# EthTransformers.net
KiCad netlist of a schematic drawn in Altium Designer
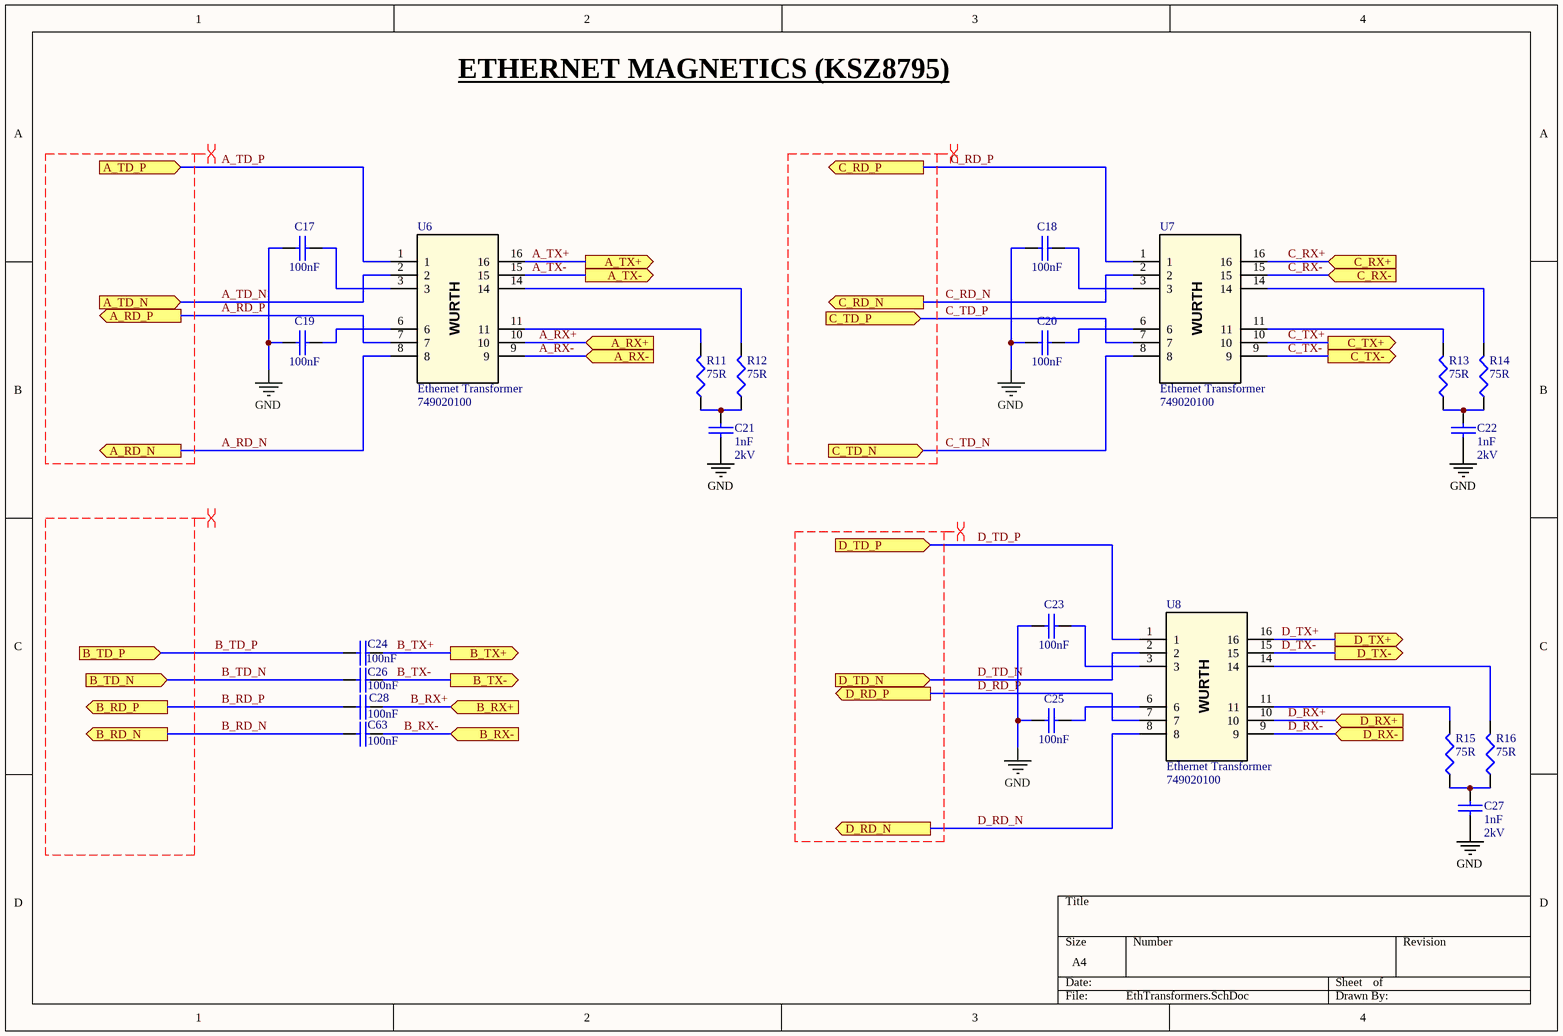
[diagram p0: EthTransformers.SchDoc]

(export (version "E")
  (design (tool "Eeschema 10.0.6"))
  (components
    (comp (ref "C17")
      (value "Capacitor")
      (footprint "CAP0402")
      (fields
        (field (name "MANUFACTURER") "TDK")
        (field (name "MANUFACTURER PART NUMBER") "CGA2B3X7R1H104K050BB")
        (field (name "CAPACITANCE") "100nF")
        (field (name "TOLERANCE") "10%")
      )
      (libsource (lib "BPL-ShematicLibrary") (part "Capacitor"))
    )
    (comp (ref "C18")
      (value "Capacitor")
      (footprint "CAP0402")
      (fields
        (field (name "MANUFACTURER") "TDK")
        (field (name "MANUFACTURER PART NUMBER") "CGA2B3X7R1H104K050BB")
        (field (name "CAPACITANCE") "100nF")
        (field (name "TOLERANCE") "10%")
      )
      (libsource (lib "BPL-ShematicLibrary") (part "Capacitor"))
    )
    (comp (ref "C19")
      (value "Capacitor")
      (footprint "CAP0402")
      (fields
        (field (name "MANUFACTURER") "TDK")
        (field (name "MANUFACTURER PART NUMBER") "CGA2B3X7R1H104K050BB")
        (field (name "CAPACITANCE") "100nF")
        (field (name "TOLERANCE") "10%")
      )
      (libsource (lib "BPL-ShematicLibrary") (part "Capacitor"))
    )
    (comp (ref "C20")
      (value "Capacitor")
      (footprint "CAP0402")
      (fields
        (field (name "MANUFACTURER") "TDK")
        (field (name "MANUFACTURER PART NUMBER") "CGA2B3X7R1H104K050BB")
        (field (name "CAPACITANCE") "100nF")
        (field (name "TOLERANCE") "10%")
      )
      (libsource (lib "BPL-ShematicLibrary") (part "Capacitor"))
    )
    (comp (ref "C21")
      (value "Capacitor")
      (footprint "CAP1206")
      (fields (field (name "CAPACITANCE") "1nF") (field (name "VOLTAGE RATING (DC)") "2kV"))
      (libsource (lib "BPL-ShematicLibrary") (part "Capacitor"))
    )
    (comp (ref "C22")
      (value "Capacitor")
      (footprint "CAP1206")
      (fields (field (name "CAPACITANCE") "1nF") (field (name "VOLTAGE RATING (DC)") "2kV"))
      (libsource (lib "BPL-ShematicLibrary") (part "Capacitor"))
    )
    (comp (ref "C23")
      (value "Capacitor")
      (footprint "CAP0402")
      (fields
        (field (name "MANUFACTURER") "TDK")
        (field (name "MANUFACTURER PART NUMBER") "CGA2B3X7R1H104K050BB")
        (field (name "CAPACITANCE") "100nF")
        (field (name "TOLERANCE") "10%")
      )
      (libsource (lib "BPL-ShematicLibrary") (part "Capacitor"))
    )
    (comp (ref "C24")
      (value "Capacitor")
      (footprint "CAP0402")
      (fields
        (field (name "MANUFACTURER") "TDK")
        (field (name "MANUFACTURER PART NUMBER") "CGA2B3X7R1H104K050BB")
        (field (name "CAPACITANCE") "100nF")
        (field (name "TOLERANCE") "10%")
      )
      (libsource (lib "BPL-ShematicLibrary") (part "Capacitor"))
    )
    (comp (ref "C25")
      (value "Capacitor")
      (footprint "CAP0402")
      (fields
        (field (name "MANUFACTURER") "TDK")
        (field (name "MANUFACTURER PART NUMBER") "CGA2B3X7R1H104K050BB")
        (field (name "CAPACITANCE") "100nF")
        (field (name "TOLERANCE") "10%")
      )
      (libsource (lib "BPL-ShematicLibrary") (part "Capacitor"))
    )
    (comp (ref "C26")
      (value "Capacitor")
      (footprint "CAP0402")
      (fields
        (field (name "MANUFACTURER") "TDK")
        (field (name "MANUFACTURER PART NUMBER") "CGA2B3X7R1H104K050BB")
        (field (name "CAPACITANCE") "100nF")
        (field (name "TOLERANCE") "10%")
      )
      (libsource (lib "BPL-ShematicLibrary") (part "Capacitor"))
    )
    (comp (ref "C27")
      (value "Capacitor")
      (footprint "CAP1206")
      (fields (field (name "CAPACITANCE") "1nF") (field (name "VOLTAGE RATING (DC)") "2kV"))
      (libsource (lib "BPL-ShematicLibrary") (part "Capacitor"))
    )
    (comp (ref "C28")
      (value "Capacitor")
      (footprint "CAP0402")
      (fields
        (field (name "MANUFACTURER") "TDK")
        (field (name "MANUFACTURER PART NUMBER") "CGA2B3X7R1H104K050BB")
        (field (name "CAPACITANCE") "100nF")
        (field (name "TOLERANCE") "10%")
      )
      (libsource (lib "BPL-ShematicLibrary") (part "Capacitor"))
    )
    (comp (ref "C63")
      (value "Capacitor")
      (footprint "CAP0402")
      (fields
        (field (name "MANUFACTURER") "TDK")
        (field (name "MANUFACTURER PART NUMBER") "CGA2B3X7R1H104K050BB")
        (field (name "CAPACITANCE") "100nF")
        (field (name "TOLERANCE") "10%")
      )
      (libsource (lib "BPL-ShematicLibrary") (part "Capacitor"))
    )
    (comp (ref "R11")
      (value "Res")
      (footprint "RES0402")
      (description "Resistor")
      (fields
        (field (name "MANUFACTURER") "Yageo")
        (field (name "MANUFACTURER PART NUMBER") "RC0402FR-0775RL")
        (field (name "RESISTANCE") "75R")
      )
      (libsource (lib "BPL-ShematicLibrary") (part "Resistor"))
    )
    (comp (ref "R12")
      (value "Res")
      (footprint "RES0402")
      (description "Resistor")
      (fields
        (field (name "MANUFACTURER") "Yageo")
        (field (name "MANUFACTURER PART NUMBER") "RC0402FR-0775RL")
        (field (name "RESISTANCE") "75R")
      )
      (libsource (lib "BPL-ShematicLibrary") (part "Resistor"))
    )
    (comp (ref "R13")
      (value "Res")
      (footprint "RES0402")
      (description "Resistor")
      (fields
        (field (name "MANUFACTURER") "Yageo")
        (field (name "MANUFACTURER PART NUMBER") "RC0402FR-0775RL")
        (field (name "RESISTANCE") "75R")
      )
      (libsource (lib "BPL-ShematicLibrary") (part "Resistor"))
    )
    (comp (ref "R14")
      (value "Res")
      (footprint "RES0402")
      (description "Resistor")
      (fields
        (field (name "MANUFACTURER") "Yageo")
        (field (name "MANUFACTURER PART NUMBER") "RC0402FR-0775RL")
        (field (name "RESISTANCE") "75R")
      )
      (libsource (lib "BPL-ShematicLibrary") (part "Resistor"))
    )
    (comp (ref "R15")
      (value "Res")
      (footprint "RES0402")
      (description "Resistor")
      (fields
        (field (name "MANUFACTURER") "Yageo")
        (field (name "MANUFACTURER PART NUMBER") "RC0402FR-0775RL")
        (field (name "RESISTANCE") "75R")
      )
      (libsource (lib "BPL-ShematicLibrary") (part "Resistor"))
    )
    (comp (ref "R16")
      (value "Res")
      (footprint "RES0402")
      (description "Resistor")
      (fields
        (field (name "MANUFACTURER") "Yageo")
        (field (name "MANUFACTURER PART NUMBER") "RC0402FR-0775RL")
        (field (name "RESISTANCE") "75R")
      )
      (libsource (lib "BPL-ShematicLibrary") (part "Resistor"))
    )
    (comp (ref "U6")
      (value "Ethernet Transformer")
      (footprint "749020100")
      (description "350µH LAN 10/100/1000 Base-T Pulse Transformer 1:1 Surface Mount")
      (fields (field (name "MANUFACTURER PART NUMBER 1") "749020100"))
      (libsource (lib "BPL-ShematicLibrary") (part "749020100"))
    )
    (comp (ref "U7")
      (value "Ethernet Transformer")
      (footprint "749020100")
      (description "350µH LAN 10/100/1000 Base-T Pulse Transformer 1:1 Surface Mount")
      (fields (field (name "MANUFACTURER PART NUMBER 1") "749020100"))
      (libsource (lib "BPL-ShematicLibrary") (part "749020100"))
    )
    (comp (ref "U8")
      (value "Ethernet Transformer")
      (footprint "749020100")
      (description "350µH LAN 10/100/1000 Base-T Pulse Transformer 1:1 Surface Mount")
      (fields (field (name "MANUFACTURER PART NUMBER 1") "749020100"))
      (libsource (lib "BPL-ShematicLibrary") (part "749020100"))
    )
  )
  (nets
    (net (code "1") (name "/A_RD_N") (class "Default")
      (node (ref "U6") (pin "8") (pinfunction "8_8") (pintype "passive"))
    )
    (net (code "2") (name "/A_RD_P") (class "Default")
      (node (ref "U6") (pin "7") (pinfunction "7_7") (pintype "passive"))
    )
    (net (code "3") (name "/A_RX+") (class "Default")
      (node (ref "U6") (pin "10") (pinfunction "10_10") (pintype "passive"))
    )
    (net (code "4") (name "/A_RX-") (class "Default")
      (node (ref "U6") (pin "9") (pinfunction "9_9") (pintype "passive"))
    )
    (net (code "5") (name "/A_TD_N") (class "Default")
      (node (ref "U6") (pin "2") (pinfunction "2_2") (pintype "passive"))
    )
    (net (code "6") (name "/A_TD_P") (class "Default")
      (node (ref "U6") (pin "1") (pinfunction "1_1") (pintype "passive"))
    )
    (net (code "7") (name "/A_TX+") (class "Default")
      (node (ref "U6") (pin "16") (pinfunction "16_16") (pintype "passive"))
    )
    (net (code "8") (name "/A_TX-") (class "Default")
      (node (ref "U6") (pin "15") (pinfunction "15_15") (pintype "passive"))
    )
    (net (code "9") (name "/B_RD_N") (class "Default")
      (node (ref "C63") (pin "2") (pinfunction "2_2") (pintype "passive"))
    )
    (net (code "10") (name "/B_RD_P") (class "Default")
      (node (ref "C28") (pin "2") (pinfunction "2_2") (pintype "passive"))
    )
    (net (code "11") (name "/B_RX+") (class "Default")
      (node (ref "C28") (pin "1") (pinfunction "1_1") (pintype "passive"))
    )
    (net (code "12") (name "/B_RX-") (class "Default")
      (node (ref "C63") (pin "1") (pinfunction "1_1") (pintype "passive"))
    )
    (net (code "13") (name "/B_TD_N") (class "Default")
      (node (ref "C26") (pin "2") (pinfunction "2_2") (pintype "passive"))
    )
    (net (code "14") (name "/B_TD_P") (class "Default")
      (node (ref "C24") (pin "2") (pinfunction "2_2") (pintype "passive"))
    )
    (net (code "15") (name "/B_TX+") (class "Default")
      (node (ref "C24") (pin "1") (pinfunction "1_1") (pintype "passive"))
    )
    (net (code "16") (name "/B_TX-") (class "Default")
      (node (ref "C26") (pin "1") (pinfunction "1_1") (pintype "passive"))
    )
    (net (code "17") (name "/C_RD_N") (class "Default")
      (node (ref "U7") (pin "2") (pinfunction "2_2") (pintype "passive"))
    )
    (net (code "18") (name "/C_RD_P") (class "Default")
      (node (ref "U7") (pin "1") (pinfunction "1_1") (pintype "passive"))
    )
    (net (code "19") (name "/C_RX+") (class "Default")
      (node (ref "U7") (pin "16") (pinfunction "16_16") (pintype "passive"))
    )
    (net (code "20") (name "/C_RX-") (class "Default")
      (node (ref "U7") (pin "15") (pinfunction "15_15") (pintype "passive"))
    )
    (net (code "21") (name "/C_TD_N") (class "Default")
      (node (ref "U7") (pin "8") (pinfunction "8_8") (pintype "passive"))
    )
    (net (code "22") (name "/C_TD_P") (class "Default")
      (node (ref "U7") (pin "7") (pinfunction "7_7") (pintype "passive"))
    )
    (net (code "23") (name "/C_TX+") (class "Default")
      (node (ref "U7") (pin "10") (pinfunction "10_10") (pintype "passive"))
    )
    (net (code "24") (name "/C_TX-") (class "Default")
      (node (ref "U7") (pin "9") (pinfunction "9_9") (pintype "passive"))
    )
    (net (code "25") (name "/D_RD_N") (class "Default")
      (node (ref "U8") (pin "8") (pinfunction "8_8") (pintype "passive"))
    )
    (net (code "26") (name "/D_RD_P") (class "Default")
      (node (ref "U8") (pin "7") (pinfunction "7_7") (pintype "passive"))
    )
    (net (code "27") (name "/D_RX+") (class "Default")
      (node (ref "U8") (pin "10") (pinfunction "10_10") (pintype "passive"))
    )
    (net (code "28") (name "/D_RX-") (class "Default")
      (node (ref "U8") (pin "9") (pinfunction "9_9") (pintype "passive"))
    )
    (net (code "29") (name "/D_TD_N") (class "Default")
      (node (ref "U8") (pin "2") (pinfunction "2_2") (pintype "passive"))
    )
    (net (code "30") (name "/D_TD_P") (class "Default")
      (node (ref "U8") (pin "1") (pinfunction "1_1") (pintype "passive"))
    )
    (net (code "31") (name "/D_TX+") (class "Default")
      (node (ref "U8") (pin "16") (pinfunction "16_16") (pintype "passive"))
    )
    (net (code "32") (name "/D_TX-") (class "Default")
      (node (ref "U8") (pin "15") (pinfunction "15_15") (pintype "passive"))
    )
    (net (code "33") (name "GND") (class "Default")
      (node (ref "C17") (pin "2") (pinfunction "2_2") (pintype "passive"))
      (node (ref "C18") (pin "2") (pinfunction "2_2") (pintype "passive"))
      (node (ref "C19") (pin "2") (pinfunction "2_2") (pintype "passive"))
      (node (ref "C20") (pin "2") (pinfunction "2_2") (pintype "passive"))
      (node (ref "C21") (pin "2") (pinfunction "2_2") (pintype "passive"))
      (node (ref "C22") (pin "2") (pinfunction "2_2") (pintype "passive"))
      (node (ref "C23") (pin "2") (pinfunction "2_2") (pintype "passive"))
      (node (ref "C25") (pin "2") (pinfunction "2_2") (pintype "passive"))
      (node (ref "C27") (pin "2") (pinfunction "2_2") (pintype "passive"))
    )
    (net (code "34") (name "Net-(C17-Pad1)") (class "Default")
      (node (ref "C17") (pin "1") (pinfunction "1_1") (pintype "passive"))
      (node (ref "U6") (pin "3") (pinfunction "3_3") (pintype "passive"))
    )
    (net (code "35") (name "Net-(C18-Pad1)") (class "Default")
      (node (ref "C18") (pin "1") (pinfunction "1_1") (pintype "passive"))
      (node (ref "U7") (pin "3") (pinfunction "3_3") (pintype "passive"))
    )
    (net (code "36") (name "Net-(C19-Pad1)") (class "Default")
      (node (ref "C19") (pin "1") (pinfunction "1_1") (pintype "passive"))
      (node (ref "U6") (pin "6") (pinfunction "6_6") (pintype "passive"))
    )
    (net (code "37") (name "Net-(C20-Pad1)") (class "Default")
      (node (ref "C20") (pin "1") (pinfunction "1_1") (pintype "passive"))
      (node (ref "U7") (pin "6") (pinfunction "6_6") (pintype "passive"))
    )
    (net (code "38") (name "Net-(C21-Pad1)") (class "Default")
      (node (ref "C21") (pin "1") (pinfunction "1_1") (pintype "passive"))
      (node (ref "R11") (pin "1") (pinfunction "1_1") (pintype "passive"))
      (node (ref "R12") (pin "1") (pinfunction "1_1") (pintype "passive"))
    )
    (net (code "39") (name "Net-(C22-Pad1)") (class "Default")
      (node (ref "C22") (pin "1") (pinfunction "1_1") (pintype "passive"))
      (node (ref "R13") (pin "1") (pinfunction "1_1") (pintype "passive"))
      (node (ref "R14") (pin "1") (pinfunction "1_1") (pintype "passive"))
    )
    (net (code "40") (name "Net-(C23-Pad1)") (class "Default")
      (node (ref "C23") (pin "1") (pinfunction "1_1") (pintype "passive"))
      (node (ref "U8") (pin "3") (pinfunction "3_3") (pintype "passive"))
    )
    (net (code "41") (name "Net-(C25-Pad1)") (class "Default")
      (node (ref "C25") (pin "1") (pinfunction "1_1") (pintype "passive"))
      (node (ref "U8") (pin "6") (pinfunction "6_6") (pintype "passive"))
    )
    (net (code "42") (name "Net-(C27-Pad1)") (class "Default")
      (node (ref "C27") (pin "1") (pinfunction "1_1") (pintype "passive"))
      (node (ref "R15") (pin "1") (pinfunction "1_1") (pintype "passive"))
      (node (ref "R16") (pin "1") (pinfunction "1_1") (pintype "passive"))
    )
    (net (code "43") (name "Net-(R11-Pad2)") (class "Default")
      (node (ref "R11") (pin "2") (pinfunction "2_2") (pintype "passive"))
      (node (ref "U6") (pin "11") (pinfunction "11_11") (pintype "passive"))
    )
    (net (code "44") (name "Net-(R12-Pad2)") (class "Default")
      (node (ref "R12") (pin "2") (pinfunction "2_2") (pintype "passive"))
      (node (ref "U6") (pin "14") (pinfunction "14_14") (pintype "passive"))
    )
    (net (code "45") (name "Net-(R13-Pad2)") (class "Default")
      (node (ref "R13") (pin "2") (pinfunction "2_2") (pintype "passive"))
      (node (ref "U7") (pin "11") (pinfunction "11_11") (pintype "passive"))
    )
    (net (code "46") (name "Net-(R14-Pad2)") (class "Default")
      (node (ref "R14") (pin "2") (pinfunction "2_2") (pintype "passive"))
      (node (ref "U7") (pin "14") (pinfunction "14_14") (pintype "passive"))
    )
    (net (code "47") (name "Net-(R15-Pad2)") (class "Default")
      (node (ref "R15") (pin "2") (pinfunction "2_2") (pintype "passive"))
      (node (ref "U8") (pin "11") (pinfunction "11_11") (pintype "passive"))
    )
    (net (code "48") (name "Net-(R16-Pad2)") (class "Default")
      (node (ref "R16") (pin "2") (pinfunction "2_2") (pintype "passive"))
      (node (ref "U8") (pin "14") (pinfunction "14_14") (pintype "passive"))
    )
  )
)
